# sparkfun-mlx90640-qwiic-breakout.net
KiCad netlist of a schematic drawn in EAGLE
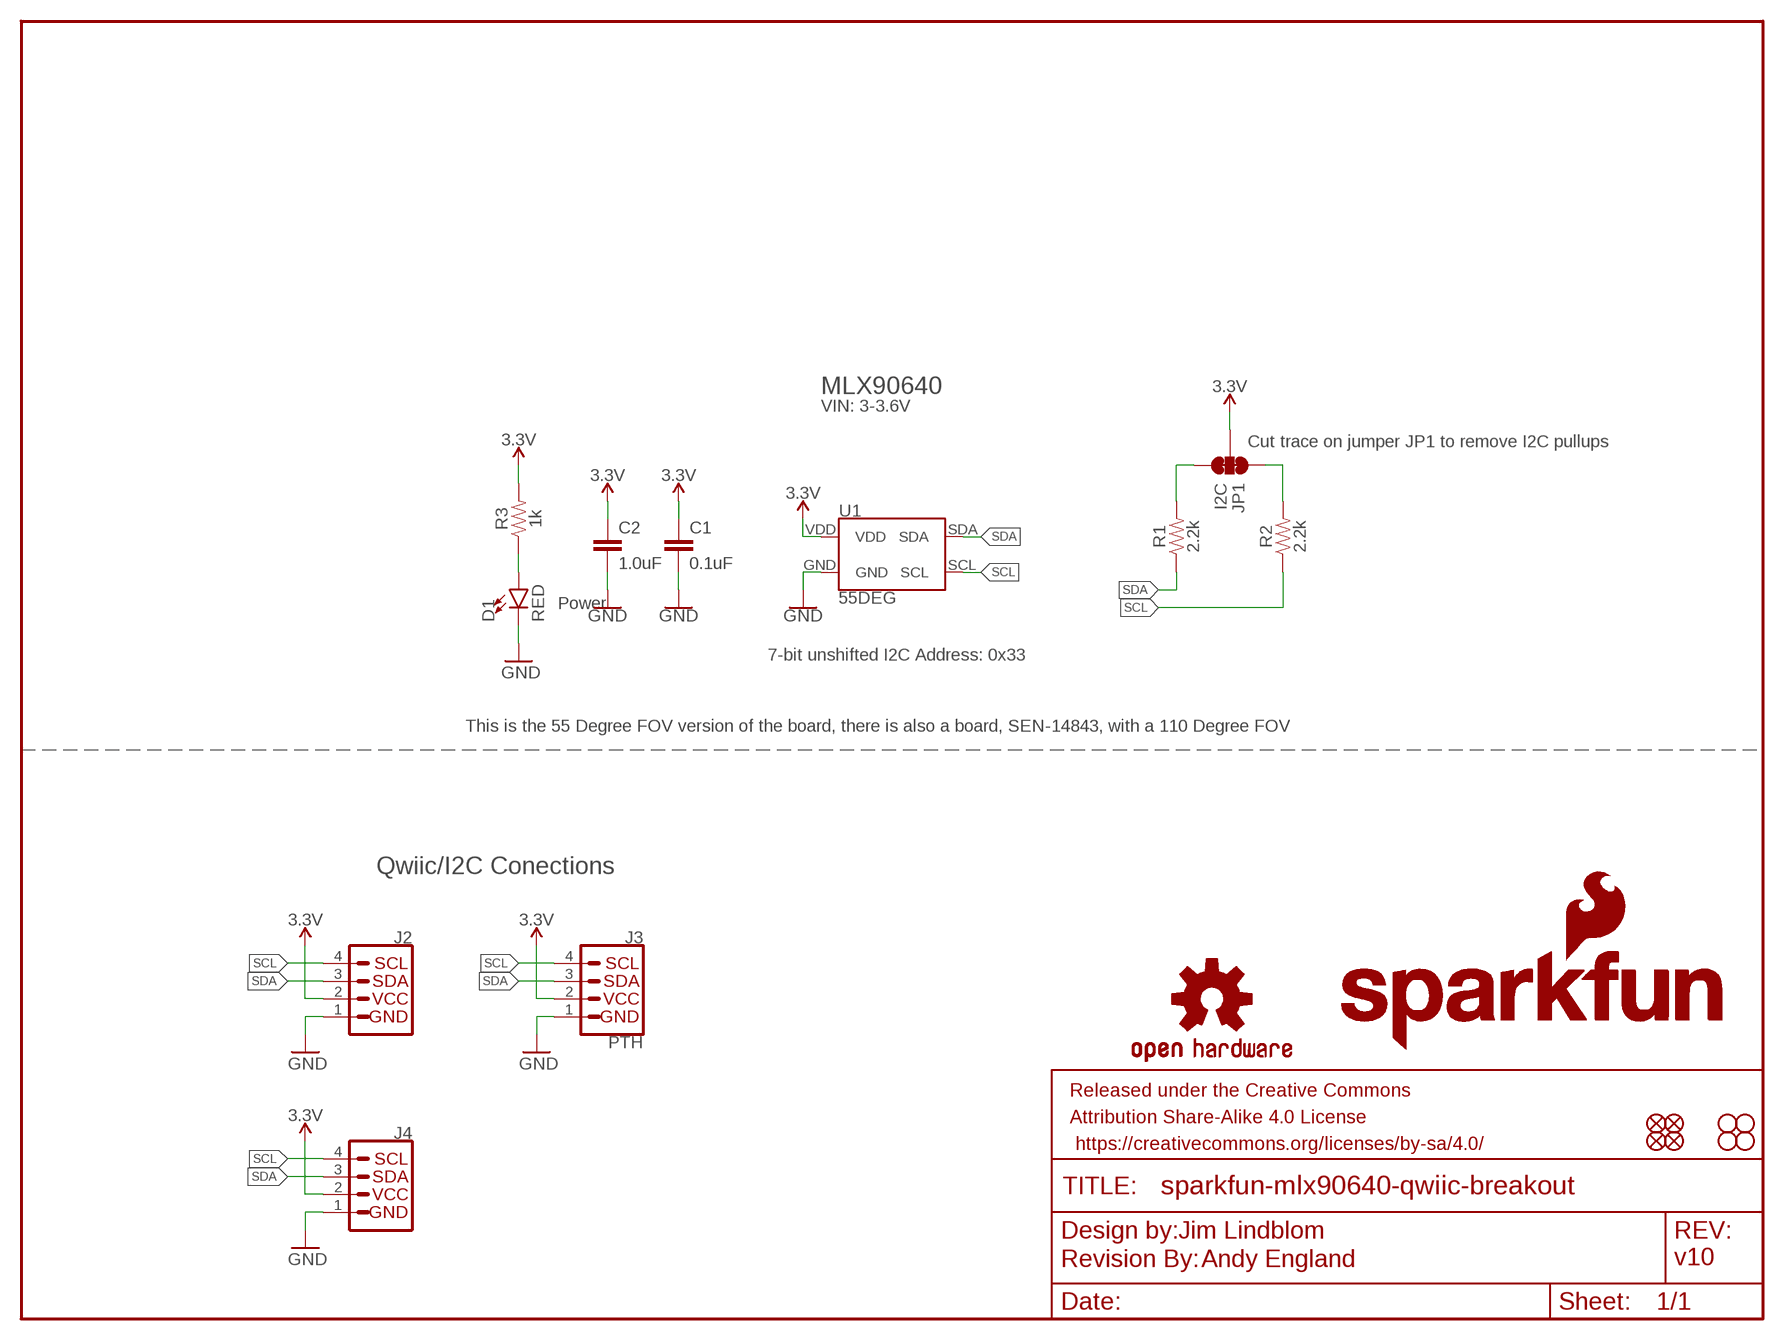
[diagram p0: schematic, sheet 1]

(export (version "E")
  (design (tool "Eeschema 10.0.6"))
  (components
    (comp (ref "C1")
      (value "0.1uF")
      (footprint "eagle-import:0603")
      (libsource (lib "eagle-import") (part "0.1UF-0603-25V-(+80/-20%)"))
    )
    (comp (ref "C2")
      (value "1.0uF")
      (footprint "eagle-import:0603")
      (libsource (lib "eagle-import") (part "1.0UF-0603-16V-10%"))
    )
    (comp (ref "D1")
      (value "RED")
      (footprint "eagle-import:LED-0603")
      (libsource (lib "eagle-import") (part "LED-RED0603"))
    )
    (comp (ref "FRAME1")
      (value "FRAME-LETTER")
      (footprint "eagle-import:CREATIVE_COMMONS")
      (libsource (lib "eagle-import") (part "FRAME-LETTER"))
    )
    (comp (ref "J2")
      (value "QWIIC_CONNECTORJS-1MM")
      (footprint "eagle-import:1X04_1MM_RA")
      (libsource (lib "eagle-import") (part "QWIIC_CONNECTORJS-1MM"))
    )
    (comp (ref "J3")
      (value "PTH")
      (footprint "eagle-import:1X04_NO_SILK")
      (libsource (lib "eagle-import") (part "I2C_STANDARD_NO_SILK"))
    )
    (comp (ref "J4")
      (value "QWIIC_CONNECTORJS-1MM")
      (footprint "eagle-import:1X04_1MM_RA")
      (libsource (lib "eagle-import") (part "QWIIC_CONNECTORJS-1MM"))
    )
    (comp (ref "JP1")
      (value "I2C")
      (footprint "eagle-import:SMT-JUMPER_3_2-NC_TRACE_NO-SILK")
      (libsource (lib "eagle-import") (part "JUMPER-SMT_3_2-NC_TRACE_NO-SILK"))
    )
    (comp (ref "JP2")
      (value "FIDUCIALUFIDUCIAL")
      (footprint "eagle-import:MICRO-FIDUCIAL")
      (libsource (lib "eagle-import") (part "FIDUCIALUFIDUCIAL"))
    )
    (comp (ref "JP3")
      (value "STAND-OFF")
      (footprint "eagle-import:STAND-OFF")
      (libsource (lib "eagle-import") (part "STAND-OFF"))
    )
    (comp (ref "JP4")
      (value "STAND-OFF")
      (footprint "eagle-import:STAND-OFF")
      (libsource (lib "eagle-import") (part "STAND-OFF"))
    )
    (comp (ref "JP5")
      (value "FIDUCIALUFIDUCIAL")
      (footprint "eagle-import:MICRO-FIDUCIAL")
      (libsource (lib "eagle-import") (part "FIDUCIALUFIDUCIAL"))
    )
    (comp (ref "JP6")
      (value "FIDUCIALUFIDUCIAL")
      (footprint "eagle-import:MICRO-FIDUCIAL")
      (libsource (lib "eagle-import") (part "FIDUCIALUFIDUCIAL"))
    )
    (comp (ref "JP7")
      (value "FIDUCIALUFIDUCIAL")
      (footprint "eagle-import:MICRO-FIDUCIAL")
      (libsource (lib "eagle-import") (part "FIDUCIALUFIDUCIAL"))
    )
    (comp (ref "JP8")
      (value "STAND-OFF")
      (footprint "eagle-import:STAND-OFF")
      (libsource (lib "eagle-import") (part "STAND-OFF"))
    )
    (comp (ref "JP9")
      (value "STAND-OFF")
      (footprint "eagle-import:STAND-OFF")
      (libsource (lib "eagle-import") (part "STAND-OFF"))
    )
    (comp (ref "LOGO1")
      (value "OSHW-LOGOMINI")
      (footprint "eagle-import:OSHW-LOGO-MINI")
      (libsource (lib "eagle-import") (part "OSHW-LOGOMINI"))
    )
    (comp (ref "LOGO2")
      (value "SFE_LOGO_NAME_FLAME.1_INCH")
      (footprint "eagle-import:SFE_LOGO_NAME_FLAME_.1")
      (libsource (lib "eagle-import") (part "SFE_LOGO_NAME_FLAME.1_INCH"))
    )
    (comp (ref "LOGO3")
      (value "SFE_LOGO_NAME.1_INCH")
      (footprint "eagle-import:SFE_LOGO_NAME_.1")
      (libsource (lib "eagle-import") (part "SFE_LOGO_NAME.1_INCH"))
    )
    (comp (ref "LOGO4")
      (value "REVISION")
      (footprint "eagle-import:REVISION")
      (libsource (lib "eagle-import") (part "REVISION"))
    )
    (comp (ref "R1")
      (value "2.2k")
      (footprint "eagle-import:0603")
      (libsource (lib "eagle-import") (part "2.2KOHM-0603-1/10W-1%"))
    )
    (comp (ref "R2")
      (value "2.2k")
      (footprint "eagle-import:0603")
      (libsource (lib "eagle-import") (part "2.2KOHM-0603-1/10W-1%"))
    )
    (comp (ref "R3")
      (value "1k")
      (footprint "eagle-import:0603")
      (libsource (lib "eagle-import") (part "1KOHM-0603-1/10W-1%"))
    )
    (comp (ref "U1")
      (value "55DEG")
      (footprint "eagle-import:MLX90540_MLX90640")
      (libsource (lib "eagle-import") (part "MLX90540_MLX90640"))
    )
  )
  (nets
    (net (code "1") (name "3.3V") (class "Default")
      (node (ref "C1") (pin "1") (pinfunction "1_1") (pintype "passive"))
      (node (ref "C2") (pin "1") (pinfunction "1_1") (pintype "passive"))
      (node (ref "J2") (pin "2") (pinfunction "2_2") (pintype "power_in"))
      (node (ref "J3") (pin "2") (pinfunction "VCC_2") (pintype "power_in"))
      (node (ref "J4") (pin "2") (pinfunction "2_2") (pintype "power_in"))
      (node (ref "JP1") (pin "2") (pinfunction "2_2") (pintype "passive"))
      (node (ref "R3") (pin "2") (pinfunction "2_2") (pintype "passive"))
      (node (ref "U1") (pin "VDD") (pinfunction "VDD_VDD") (pintype "bidirectional"))
    )
    (net (code "2") (name "GND") (class "Default")
      (node (ref "C1") (pin "2") (pinfunction "2_2") (pintype "passive"))
      (node (ref "C2") (pin "2") (pinfunction "2_2") (pintype "passive"))
      (node (ref "D1") (pin "C") (pinfunction "C_C") (pintype "passive"))
      (node (ref "J2") (pin "1") (pinfunction "1_1") (pintype "power_in"))
      (node (ref "J3") (pin "1") (pinfunction "GND_1") (pintype "power_in"))
      (node (ref "J4") (pin "1") (pinfunction "1_1") (pintype "power_in"))
      (node (ref "U1") (pin "GND") (pinfunction "GND_GND") (pintype "bidirectional"))
    )
    (net (code "3") (name "Net-(D1-PadA)") (class "Default")
      (node (ref "D1") (pin "A") (pinfunction "A_A") (pintype "passive"))
      (node (ref "R3") (pin "1") (pinfunction "1_1") (pintype "passive"))
    )
    (net (code "4") (name "Net-(JP1-Pad1)") (class "Default")
      (node (ref "JP1") (pin "1") (pinfunction "1_1") (pintype "passive"))
      (node (ref "R2") (pin "2") (pinfunction "2_2") (pintype "passive"))
    )
    (net (code "5") (name "Net-(JP1-Pad3)") (class "Default")
      (node (ref "JP1") (pin "3") (pinfunction "3_3") (pintype "passive"))
      (node (ref "R1") (pin "2") (pinfunction "2_2") (pintype "passive"))
    )
    (net (code "6") (name "SCL") (class "Default")
      (node (ref "J2") (pin "4") (pinfunction "4_4") (pintype "passive"))
      (node (ref "J3") (pin "4") (pinfunction "SCL_4") (pintype "passive"))
      (node (ref "J4") (pin "4") (pinfunction "4_4") (pintype "passive"))
      (node (ref "R2") (pin "1") (pinfunction "1_1") (pintype "passive"))
      (node (ref "U1") (pin "SCL") (pinfunction "SCL_SCL") (pintype "bidirectional"))
    )
    (net (code "7") (name "SDA") (class "Default")
      (node (ref "J2") (pin "3") (pinfunction "3_3") (pintype "passive"))
      (node (ref "J3") (pin "3") (pinfunction "SDA_3") (pintype "passive"))
      (node (ref "J4") (pin "3") (pinfunction "3_3") (pintype "passive"))
      (node (ref "R1") (pin "1") (pinfunction "1_1") (pintype "passive"))
      (node (ref "U1") (pin "SDA") (pinfunction "SDA_SDA") (pintype "bidirectional"))
    )
  )
)
